# THS_Joule_Thief_torch.net
KiCad netlist of a schematic drawn in EAGLE
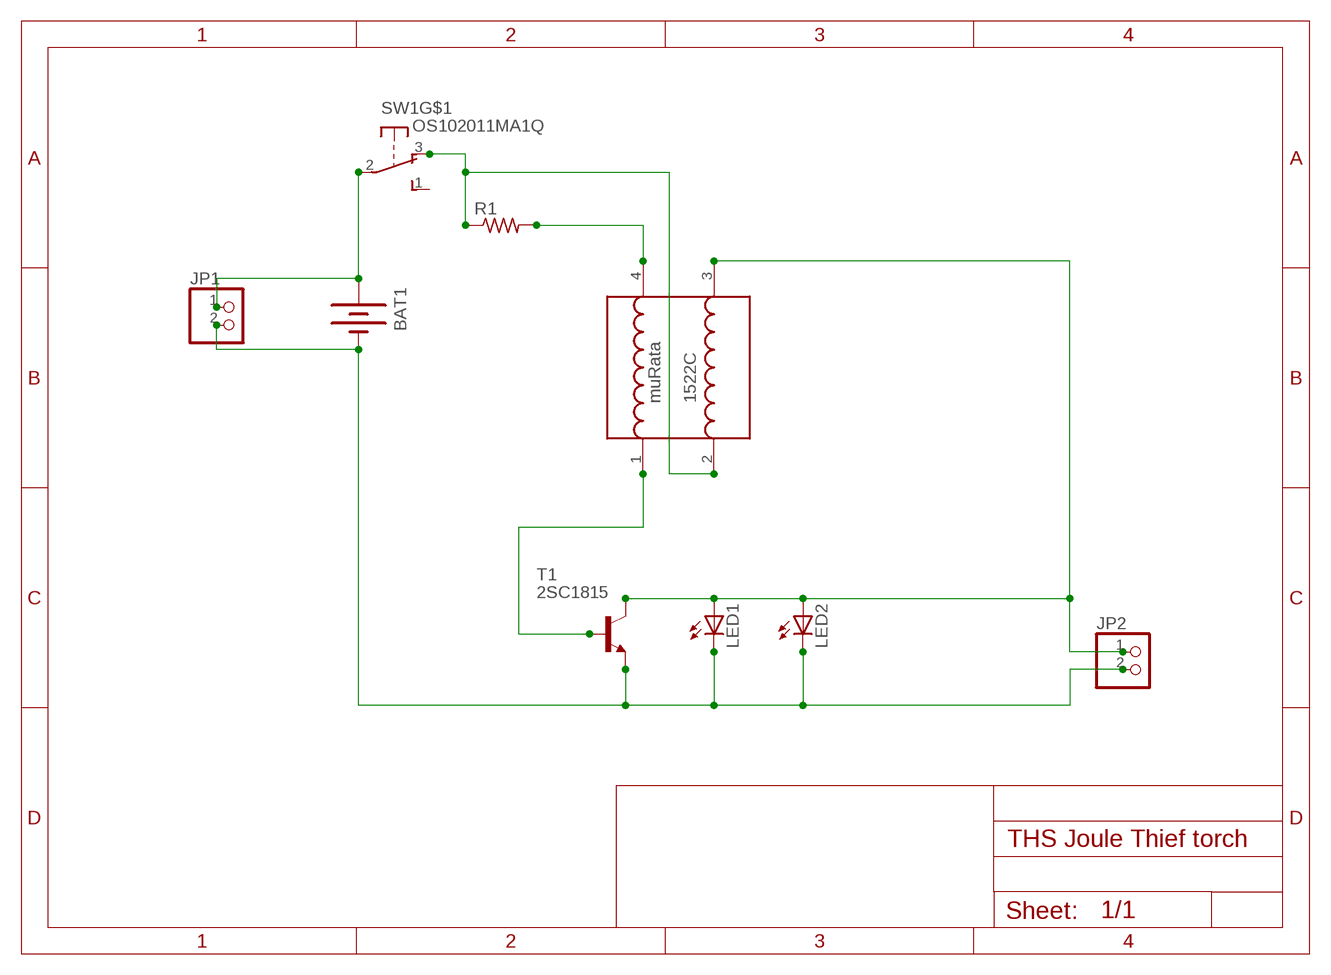
[diagram p0: schematic, sheet 1]

(export (version "E")
  (design (tool "Eeschema 10.0.6"))
  (components
    (comp (ref "BAT1")
      (value "BATTERY")
      (footprint "eagle-import:BATTERY-AA-PANEL-AKIZUKI")
      (libsource (lib "eagle-import") (part "BATTERY"))
    )
    (comp (ref "JP1")
      (value "PINHD-1X2")
      (footprint "eagle-import:1X02")
      (libsource (lib "eagle-import") (part "PINHD-1X2"))
    )
    (comp (ref "JP2")
      (value "PINHD-1X2")
      (footprint "eagle-import:1X02")
      (libsource (lib "eagle-import") (part "PINHD-1X2"))
    )
    (comp (ref "LED1")
      (value "LED5MM")
      (footprint "eagle-import:LED5MM")
      (libsource (lib "eagle-import") (part "LED5MM"))
    )
    (comp (ref "LED2")
      (value "LED5MM")
      (footprint "eagle-import:LED5MM")
      (libsource (lib "eagle-import") (part "LED5MM"))
    )
    (comp (ref "R1")
      (value "R-US_0204/7")
      (footprint "eagle-import:0204_7")
      (libsource (lib "eagle-import") (part "R-US_0204/7"))
    )
    (comp (ref "SW1")
      (value "OS102011MA1Q")
      (footprint "eagle-import:OS102011MA1Q")
      (libsource (lib "eagle-import") (part "OS102011MA1Q"))
    )
    (comp (ref "T1")
      (value "2SC1815")
      (footprint "eagle-import:TO92-ECB")
      (libsource (lib "eagle-import") (part "2SC1815"))
    )
    (comp (ref "U$1")
      (value "1522C_MURATA_AC-CHOKE")
      (footprint "eagle-import:AC-CHOKE_THROUGH_HOLE")
      (libsource (lib "eagle-import") (part "1522C_MURATA_AC-CHOKE"))
    )
  )
  (nets
    (net (code "1") (name "Net-(LED1-C)") (class "Default")
      (node (ref "BAT1") (pin "-") (pinfunction "-_-") (pintype "power_in"))
      (node (ref "JP1") (pin "2") (pinfunction "2_2") (pintype "passive"))
      (node (ref "JP2") (pin "2") (pinfunction "2_2") (pintype "passive"))
      (node (ref "LED1") (pin "K") (pinfunction "C_K") (pintype "passive"))
      (node (ref "LED2") (pin "K") (pinfunction "C_K") (pintype "passive"))
      (node (ref "T1") (pin "E") (pinfunction "E_E") (pintype "passive"))
    )
    (net (code "2") (name "Net-(SW1A-O)") (class "Default")
      (node (ref "R1") (pin "1") (pinfunction "1_1") (pintype "passive"))
      (node (ref "SW1") (pin "3") (pinfunction "O_3") (pintype "passive"))
      (node (ref "U$1") (pin "2") (pinfunction "COIL2_A_2") (pintype "bidirectional"))
    )
    (net (code "3") (name "Net-(SW1A-P)") (class "Default")
      (node (ref "BAT1") (pin "+") (pinfunction "+_+") (pintype "power_in"))
      (node (ref "JP1") (pin "1") (pinfunction "1_1") (pintype "passive"))
      (node (ref "SW1") (pin "2") (pinfunction "P_2") (pintype "passive"))
    )
    (net (code "4") (name "Net-(U$1-COIL1_A)") (class "Default")
      (node (ref "T1") (pin "B") (pinfunction "B_B") (pintype "passive"))
      (node (ref "U$1") (pin "1") (pinfunction "COIL1_A_1") (pintype "bidirectional"))
    )
    (net (code "5") (name "Net-(U$1-COIL1_B)") (class "Default")
      (node (ref "R1") (pin "2") (pinfunction "2_2") (pintype "passive"))
      (node (ref "U$1") (pin "4") (pinfunction "COIL1_B_4") (pintype "bidirectional"))
    )
    (net (code "6") (name "Net-(U$1-COIL2_B)") (class "Default")
      (node (ref "JP2") (pin "1") (pinfunction "1_1") (pintype "passive"))
      (node (ref "LED1") (pin "A") (pinfunction "A_A") (pintype "passive"))
      (node (ref "LED2") (pin "A") (pinfunction "A_A") (pintype "passive"))
      (node (ref "T1") (pin "C") (pinfunction "C_C") (pintype "passive"))
      (node (ref "U$1") (pin "3") (pinfunction "COIL2_B_3") (pintype "bidirectional"))
    )
    (net (code "7") (name "unconnected-(SW1A-S-Pad1)") (class "Default")
      (node (ref "SW1") (pin "1") (pinfunction "S_1") (pintype "passive"))
    )
  )
)
